# RP_ComputeModule3_rev_3_0_HDMi.net
KiCad netlist of a schematic drawn in Altium Designer
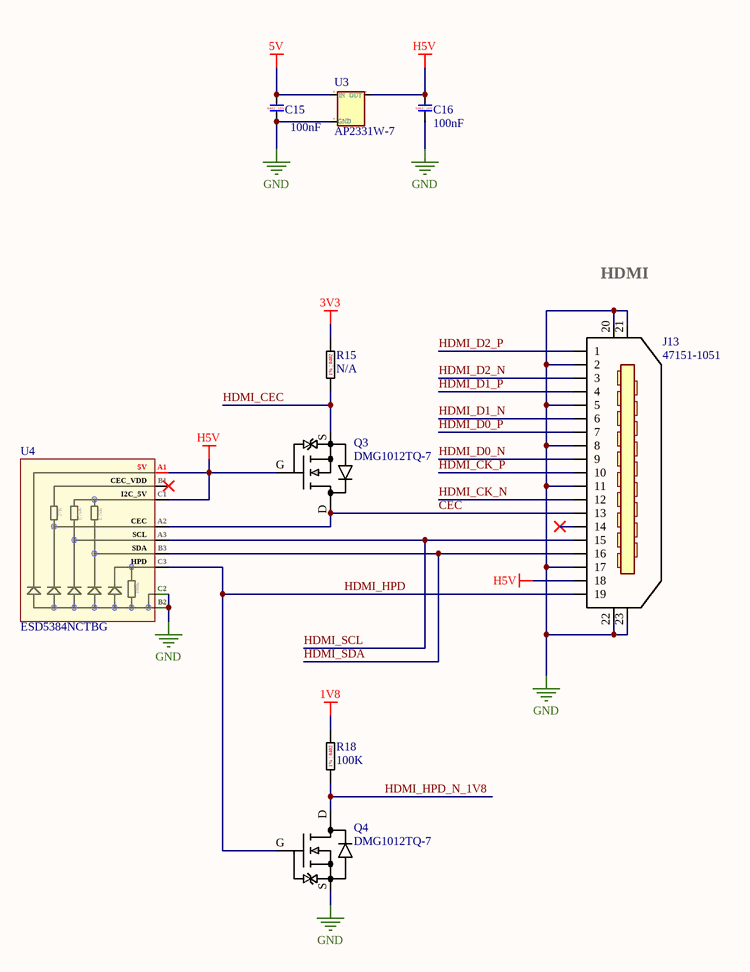
[diagram p0: RP_ComputeModule3_rev.3.0_HDMi.SchDoc]

(export (version "E")
  (design (tool "Eeschema 10.0.6"))
  (components
    (comp (ref "C15")
      (value "100nF")
      (footprint "GJM 0402 C")
      (description "Multilayer Ceramic Capacitors MLCC - SMD/SMT 0402 0.1uF 10volts 5%")
      (fields
        (field (name "MANUFACTURER") "Murata Electronics")
        (field (name "MANUFACTURER PART NUMBER") "GRM155R71A104JA01D")
      )
      (libsource (lib "Murata_Capacitors") (part "GRM155R71A104JA01D"))
    )
    (comp (ref "C16")
      (value "100nF")
      (footprint "GJM 0402 C")
      (description "Multilayer Ceramic Capacitors MLCC - SMD/SMT 0402 0.1uF 10volts 5%")
      (fields
        (field (name "MANUFACTURER") "Murata Electronics")
        (field (name "MANUFACTURER PART NUMBER") "GRM155R71A104JA01D")
      )
      (libsource (lib "Murata_Capacitors") (part "GRM155R71A104JA01D"))
    )
    (comp (ref "J13")
      (value "47151-1051")
      (footprint "Molex 471511051 HDMi")
      (description "HDMI, Displayport & DVI Connectors 1.0 HDMI RIGHT ANGLE NGLE HEADER ASSEMBLY")
      (fields (field (name "MANUFACTURER") "Molex"))
      (libsource (lib "Molex_Library") (part "47151-1051"))
    )
    (comp (ref "Q3")
      (value "DMG1012TQ-7")
      (footprint "Diodes SOT523")
      (description "MOSFET NCH 20V 630MA SOT523")
      (fields (field (name "MANUFACTURER") "Diodes"))
      (libsource (lib "Diodes_Inc_Library") (part "DMG1012TQ-7"))
    )
    (comp (ref "Q4")
      (value "DMG1012TQ-7")
      (footprint "Diodes SOT523")
      (description "MOSFET NCH 20V 630MA SOT523")
      (fields (field (name "MANUFACTURER") "Diodes"))
      (libsource (lib "Diodes_Inc_Library") (part "DMG1012TQ-7"))
    )
    (comp (ref "R15")
      (value "N/A")
      (footprint "RES0402N/A")
      (libsource (lib "KOA_Resistors") (part "Resistor_N/A"))
    )
    (comp (ref "R18")
      (value "100K")
      (footprint "RES0402")
      (description "Thick Film Resistors - SMD 0.125W 100Kohm 1% 200ppm")
      (fields
        (field (name "MANUFACTURER") "KOA Speer")
        (field (name "MANUFACTURER PART NUMBER") "SG73P1ETTP1003F")
      )
      (libsource (lib "KOA_Resistors") (part "SG73P1ETTP1003F"))
    )
    (comp (ref "U3")
      (value "AP2331W-7")
      (footprint "DiodesInc SC59-BEC")
      (description "LOAD SWITCH SC59")
      (fields (field (name "MANUFACTURER") "Diodes") (field (name "VOLTAGE") "5.2V"))
      (libsource (lib "Diodes_Inc_Library") (part "AP2331W-7"))
    )
    (comp (ref "U4")
      (value "ESD5384NCTBG")
      (footprint "ONSemi CSP-9")
      (description "TVS DIODE 3VWM 9WLCSP")
      (fields (field (name "MANUFACTURER") "ON Semiconductor"))
      (libsource (lib "OnSemiconductor_Library") (part "ESD5384NCTBG"))
    )
  )
  (nets
    (net (code "1") (name "/CEC") (class "Default")
      (node (ref "J13") (pin "13") (pinfunction "13_13") (pintype "passive"))
      (node (ref "Q3") (pin "D") (pinfunction "D_D") (pintype "passive"))
      (node (ref "U4") (pin "A2") (pinfunction "A2_A2") (pintype "passive"))
    )
    (net (code "2") (name "/HDMI_CEC") (class "Default")
      (node (ref "Q3") (pin "S") (pinfunction "S_S") (pintype "passive"))
      (node (ref "R15") (pin "2") (pinfunction "2_2") (pintype "passive"))
    )
    (net (code "3") (name "/HDMI_CK_N") (class "Default")
      (node (ref "J13") (pin "12") (pinfunction "12_12") (pintype "passive"))
    )
    (net (code "4") (name "/HDMI_CK_P") (class "Default")
      (node (ref "J13") (pin "10") (pinfunction "10_10") (pintype "passive"))
    )
    (net (code "5") (name "/HDMI_D0_N") (class "Default")
      (node (ref "J13") (pin "9") (pinfunction "9_9") (pintype "passive"))
    )
    (net (code "6") (name "/HDMI_D0_P") (class "Default")
      (node (ref "J13") (pin "7") (pinfunction "7_7") (pintype "passive"))
    )
    (net (code "7") (name "/HDMI_D1_N") (class "Default")
      (node (ref "J13") (pin "6") (pinfunction "6_6") (pintype "passive"))
    )
    (net (code "8") (name "/HDMI_D1_P") (class "Default")
      (node (ref "J13") (pin "4") (pinfunction "4_4") (pintype "passive"))
    )
    (net (code "9") (name "/HDMI_D2_N") (class "Default")
      (node (ref "J13") (pin "3") (pinfunction "3_3") (pintype "passive"))
    )
    (net (code "10") (name "/HDMI_D2_P") (class "Default")
      (node (ref "J13") (pin "1") (pinfunction "1_1") (pintype "passive"))
    )
    (net (code "11") (name "/HDMI_HPD") (class "Default")
      (node (ref "J13") (pin "19") (pinfunction "19_19") (pintype "passive"))
      (node (ref "Q4") (pin "G") (pinfunction "G_G") (pintype "passive"))
      (node (ref "U4") (pin "C3") (pinfunction "C3_C3") (pintype "passive"))
    )
    (net (code "12") (name "/HDMI_HPD_N_1V8") (class "Default")
      (node (ref "Q4") (pin "D") (pinfunction "D_D") (pintype "passive"))
      (node (ref "R18") (pin "2") (pinfunction "2_2") (pintype "passive"))
    )
    (net (code "13") (name "/HDMI_SCL") (class "Default")
      (node (ref "J13") (pin "15") (pinfunction "15_15") (pintype "passive"))
      (node (ref "U4") (pin "A3") (pinfunction "A3_A3") (pintype "passive"))
    )
    (net (code "14") (name "/HDMI_SDA") (class "Default")
      (node (ref "J13") (pin "16") (pinfunction "16_16") (pintype "passive"))
      (node (ref "U4") (pin "B3") (pinfunction "B3_B3") (pintype "passive"))
    )
    (net (code "15") (name "1V8") (class "Default")
      (node (ref "R18") (pin "1") (pinfunction "1_1") (pintype "passive"))
    )
    (net (code "16") (name "3V3") (class "Default")
      (node (ref "R15") (pin "1") (pinfunction "1_1") (pintype "passive"))
    )
    (net (code "17") (name "5V") (class "Default")
      (node (ref "C15") (pin "2") (pinfunction "2_2") (pintype "passive"))
      (node (ref "U3") (pin "IN") (pinfunction "3_IN") (pintype "passive"))
    )
    (net (code "18") (name "GND") (class "Default")
      (node (ref "C15") (pin "1") (pinfunction "1_1") (pintype "passive"))
      (node (ref "C16") (pin "1") (pinfunction "1_1") (pintype "passive"))
      (node (ref "J13") (pin "11") (pinfunction "11_11") (pintype "passive"))
      (node (ref "J13") (pin "17") (pinfunction "17_17") (pintype "passive"))
      (node (ref "J13") (pin "2") (pinfunction "2_2") (pintype "passive"))
      (node (ref "J13") (pin "20") (pinfunction "20_20") (pintype "passive"))
      (node (ref "J13") (pin "21") (pinfunction "21_21") (pintype "passive"))
      (node (ref "J13") (pin "22") (pinfunction "22_22") (pintype "passive"))
      (node (ref "J13") (pin "23") (pinfunction "23_23") (pintype "passive"))
      (node (ref "J13") (pin "5") (pinfunction "5_5") (pintype "passive"))
      (node (ref "J13") (pin "8") (pinfunction "8_8") (pintype "passive"))
      (node (ref "Q4") (pin "S") (pinfunction "S_S") (pintype "passive"))
      (node (ref "U3") (pin "GND") (pinfunction "1_GND") (pintype "passive"))
      (node (ref "U4") (pin "B2") (pinfunction "B2_B2") (pintype "passive"))
      (node (ref "U4") (pin "C2") (pinfunction "C2_C2") (pintype "passive"))
    )
    (net (code "19") (name "H5V") (class "Default")
      (node (ref "C16") (pin "2") (pinfunction "2_2") (pintype "passive"))
      (node (ref "J13") (pin "18") (pinfunction "18_18") (pintype "passive"))
      (node (ref "Q3") (pin "G") (pinfunction "G_G") (pintype "passive"))
      (node (ref "U3") (pin "OUT") (pinfunction "2_OUT") (pintype "passive"))
      (node (ref "U4") (pin "A1") (pinfunction "A1_A1") (pintype "passive"))
      (node (ref "U4") (pin "C1") (pinfunction "C1_C1") (pintype "passive"))
    )
    (net (code "20") (name "unconnected-(J13-Pad14)") (class "Default")
      (node (ref "J13") (pin "14") (pinfunction "14_14") (pintype "passive+no_connect"))
    )
    (net (code "21") (name "unconnected-(U4-PadB1)") (class "Default")
      (node (ref "U4") (pin "B1") (pinfunction "B1_B1") (pintype "passive+no_connect"))
    )
  )
)
